# pt100.net
KiCad netlist of a schematic drawn in Altium Designer
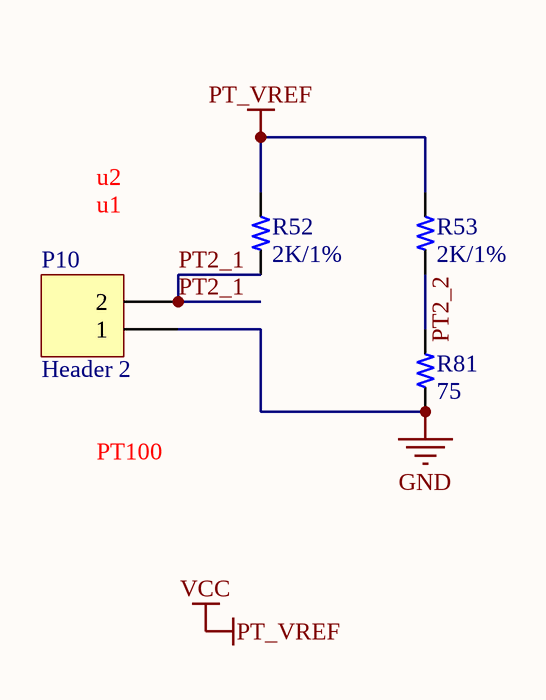
[diagram p0: pt100.SchDoc]

(export (version "E")
  (design (tool "Eeschema 10.0.6"))
  (components
    (comp (ref "P10")
      (value "Header 2")
      (footprint "KF250NH-3.5-2P")
      (fields (field (name "PUBLISHER") "Altium Limited"))
      (libsource (lib "Miscellaneous Connectors") (part "Header 2"))
    )
    (comp (ref "R52") (value "2K/1%") (footprint "0603R") (libsource (lib "JRJ_1") (part "R")))
    (comp (ref "R53") (value "2K/1%") (footprint "0603R") (libsource (lib "JRJ_1") (part "R")))
    (comp (ref "R81") (value "75") (footprint "0603R") (libsource (lib "JRJ_1") (part "R")))
  )
  (nets
    (net (code "1") (name "/PT2_1") (class "Default")
      (node (ref "P10") (pin "2") (pinfunction "2_2") (pintype "passive"))
      (node (ref "R52") (pin "1") (pintype "passive"))
    )
    (net (code "2") (name "/PT2_2") (class "Default")
      (node (ref "R53") (pin "1") (pintype "passive"))
      (node (ref "R81") (pin "2") (pintype "passive"))
    )
    (net (code "3") (name "GND") (class "Default")
      (node (ref "P10") (pin "1") (pinfunction "1_1") (pintype "passive"))
      (node (ref "R81") (pin "1") (pintype "passive"))
    )
    (net (code "4") (name "PT_VREF") (class "Default")
      (node (ref "R52") (pin "2") (pintype "passive"))
      (node (ref "R53") (pin "2") (pintype "passive"))
    )
  )
)
